# Schematics.net
KiCad netlist of a schematic drawn in EAGLE
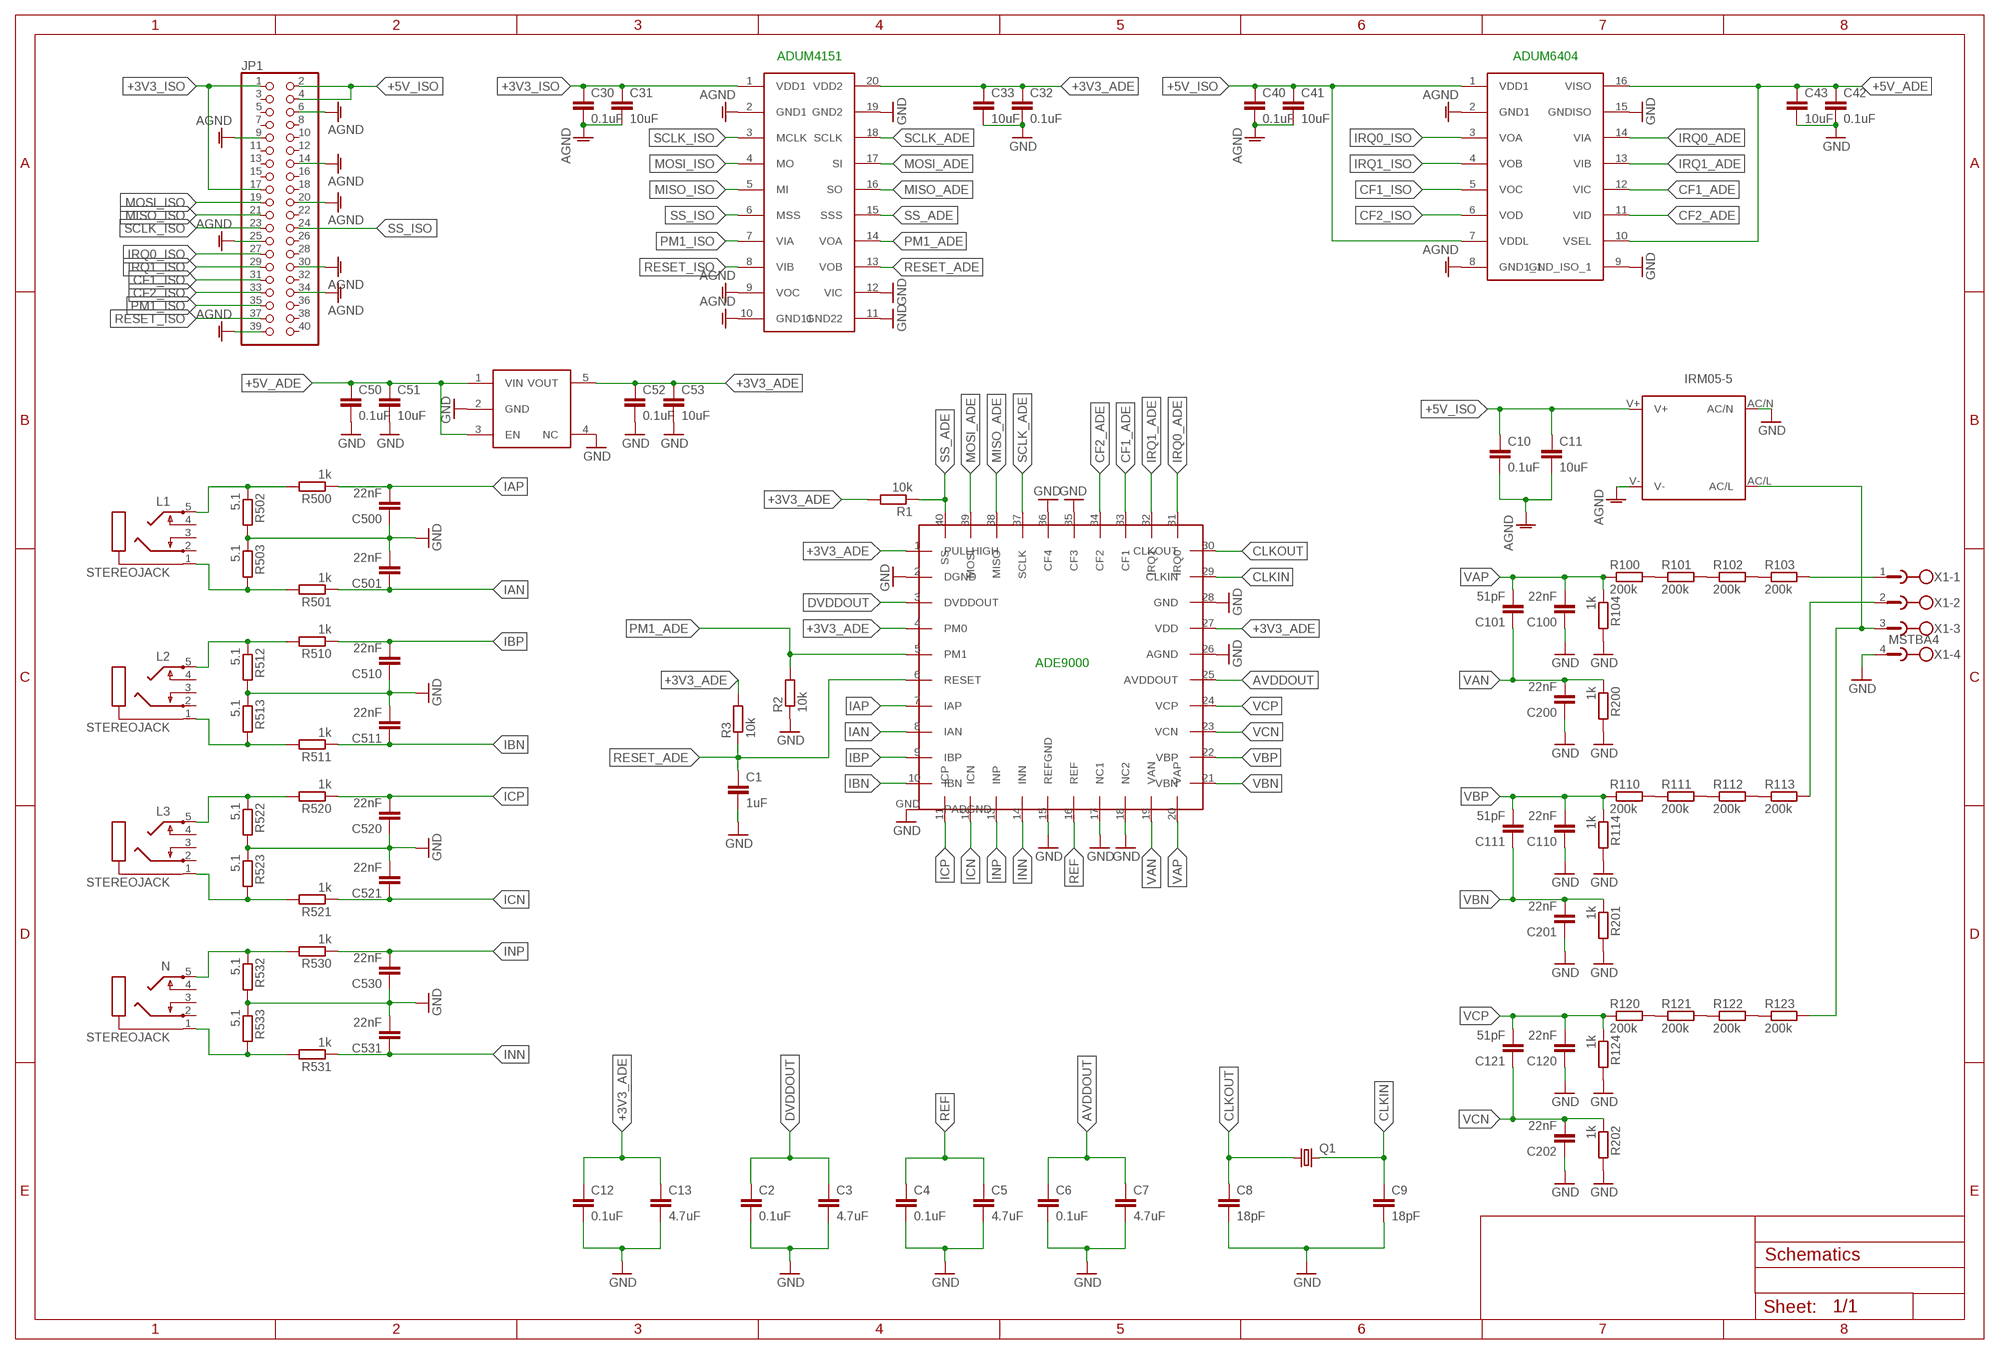
[diagram p0: schematic, sheet 1]

(export (version "E")
  (design (tool "Eeschema 10.0.6"))
  (components
    (comp (ref "ADE9000")
      (value "ADE9000")
      (footprint "eagle-import:LFCSP40")
      (libsource (lib "eagle-import") (part "ADE9000"))
    )
    (comp (ref "ADUM4151")
      (value "ADUM4151")
      (footprint "eagle-import:SOIC20R")
      (libsource (lib "eagle-import") (part "ADUM4151"))
    )
    (comp (ref "ADUM6404")
      (value "ADUM6404")
      (footprint "eagle-import:SOIC16R")
      (libsource (lib "eagle-import") (part "ADUM6404"))
    )
    (comp (ref "C1")
      (value "1uF")
      (footprint "eagle-import:C0805")
      (libsource (lib "eagle-import") (part "C-EUC0805"))
    )
    (comp (ref "C2")
      (value "0.1uF")
      (footprint "eagle-import:C0805")
      (libsource (lib "eagle-import") (part "C-EUC0805"))
    )
    (comp (ref "C3")
      (value "4.7uF")
      (footprint "eagle-import:C0805")
      (libsource (lib "eagle-import") (part "C-EUC0805"))
    )
    (comp (ref "C4")
      (value "0.1uF")
      (footprint "eagle-import:C0805")
      (libsource (lib "eagle-import") (part "C-EUC0805"))
    )
    (comp (ref "C5")
      (value "4.7uF")
      (footprint "eagle-import:C0805")
      (libsource (lib "eagle-import") (part "C-EUC0805"))
    )
    (comp (ref "C6")
      (value "0.1uF")
      (footprint "eagle-import:C0805")
      (libsource (lib "eagle-import") (part "C-EUC0805"))
    )
    (comp (ref "C7")
      (value "4.7uF")
      (footprint "eagle-import:C0805")
      (libsource (lib "eagle-import") (part "C-EUC0805"))
    )
    (comp (ref "C8")
      (value "18pF")
      (footprint "eagle-import:C0805")
      (libsource (lib "eagle-import") (part "C-EUC0805"))
    )
    (comp (ref "C9")
      (value "18pF")
      (footprint "eagle-import:C0805")
      (libsource (lib "eagle-import") (part "C-EUC0805"))
    )
    (comp (ref "C10")
      (value "0.1uF")
      (footprint "eagle-import:C0805")
      (libsource (lib "eagle-import") (part "C-EUC0805"))
    )
    (comp (ref "C11")
      (value "10uF")
      (footprint "eagle-import:C0805")
      (libsource (lib "eagle-import") (part "C-EUC0805"))
    )
    (comp (ref "C12")
      (value "0.1uF")
      (footprint "eagle-import:C0805")
      (libsource (lib "eagle-import") (part "C-EUC0805"))
    )
    (comp (ref "C13")
      (value "4.7uF")
      (footprint "eagle-import:C0805")
      (libsource (lib "eagle-import") (part "C-EUC0805"))
    )
    (comp (ref "C30")
      (value "0.1uF")
      (footprint "eagle-import:C0805")
      (libsource (lib "eagle-import") (part "C-EUC0805"))
    )
    (comp (ref "C31")
      (value "10uF")
      (footprint "eagle-import:C0805")
      (libsource (lib "eagle-import") (part "C-EUC0805"))
    )
    (comp (ref "C32")
      (value "0.1uF")
      (footprint "eagle-import:C0805")
      (libsource (lib "eagle-import") (part "C-EUC0805"))
    )
    (comp (ref "C33")
      (value "10uF")
      (footprint "eagle-import:C0805")
      (libsource (lib "eagle-import") (part "C-EUC0805"))
    )
    (comp (ref "C40")
      (value "0.1uF")
      (footprint "eagle-import:C0805")
      (libsource (lib "eagle-import") (part "C-EUC0805"))
    )
    (comp (ref "C41")
      (value "10uF")
      (footprint "eagle-import:C0805")
      (libsource (lib "eagle-import") (part "C-EUC0805"))
    )
    (comp (ref "C42")
      (value "0.1uF")
      (footprint "eagle-import:C0805")
      (libsource (lib "eagle-import") (part "C-EUC0805"))
    )
    (comp (ref "C43")
      (value "10uF")
      (footprint "eagle-import:C0805")
      (libsource (lib "eagle-import") (part "C-EUC0805"))
    )
    (comp (ref "C50")
      (value "0.1uF")
      (footprint "eagle-import:C0805")
      (libsource (lib "eagle-import") (part "C-EUC0805"))
    )
    (comp (ref "C51")
      (value "10uF")
      (footprint "eagle-import:C0805")
      (libsource (lib "eagle-import") (part "C-EUC0805"))
    )
    (comp (ref "C52")
      (value "0.1uF")
      (footprint "eagle-import:C0805")
      (libsource (lib "eagle-import") (part "C-EUC0805"))
    )
    (comp (ref "C53")
      (value "10uF")
      (footprint "eagle-import:C0805")
      (libsource (lib "eagle-import") (part "C-EUC0805"))
    )
    (comp (ref "C100")
      (value "22nF")
      (footprint "eagle-import:C0805")
      (libsource (lib "eagle-import") (part "C-EUC0805"))
    )
    (comp (ref "C101")
      (value "51pF")
      (footprint "eagle-import:C0805")
      (libsource (lib "eagle-import") (part "C-EUC0805"))
    )
    (comp (ref "C110")
      (value "22nF")
      (footprint "eagle-import:C0805")
      (libsource (lib "eagle-import") (part "C-EUC0805"))
    )
    (comp (ref "C111")
      (value "51pF")
      (footprint "eagle-import:C0805")
      (libsource (lib "eagle-import") (part "C-EUC0805"))
    )
    (comp (ref "C120")
      (value "22nF")
      (footprint "eagle-import:C0805")
      (libsource (lib "eagle-import") (part "C-EUC0805"))
    )
    (comp (ref "C121")
      (value "51pF")
      (footprint "eagle-import:C0805")
      (libsource (lib "eagle-import") (part "C-EUC0805"))
    )
    (comp (ref "C200")
      (value "22nF")
      (footprint "eagle-import:C0805")
      (libsource (lib "eagle-import") (part "C-EUC0805"))
    )
    (comp (ref "C201")
      (value "22nF")
      (footprint "eagle-import:C0805")
      (libsource (lib "eagle-import") (part "C-EUC0805"))
    )
    (comp (ref "C202")
      (value "22nF")
      (footprint "eagle-import:C0805")
      (libsource (lib "eagle-import") (part "C-EUC0805"))
    )
    (comp (ref "C500")
      (value "22nF")
      (footprint "eagle-import:C0805")
      (libsource (lib "eagle-import") (part "C-EUC0805"))
    )
    (comp (ref "C501")
      (value "22nF")
      (footprint "eagle-import:C0805")
      (libsource (lib "eagle-import") (part "C-EUC0805"))
    )
    (comp (ref "C510")
      (value "22nF")
      (footprint "eagle-import:C0805")
      (libsource (lib "eagle-import") (part "C-EUC0805"))
    )
    (comp (ref "C511")
      (value "22nF")
      (footprint "eagle-import:C0805")
      (libsource (lib "eagle-import") (part "C-EUC0805"))
    )
    (comp (ref "C520")
      (value "22nF")
      (footprint "eagle-import:C0805")
      (libsource (lib "eagle-import") (part "C-EUC0805"))
    )
    (comp (ref "C521")
      (value "22nF")
      (footprint "eagle-import:C0805")
      (libsource (lib "eagle-import") (part "C-EUC0805"))
    )
    (comp (ref "C530")
      (value "22nF")
      (footprint "eagle-import:C0805")
      (libsource (lib "eagle-import") (part "C-EUC0805"))
    )
    (comp (ref "C531")
      (value "22nF")
      (footprint "eagle-import:C0805")
      (libsource (lib "eagle-import") (part "C-EUC0805"))
    )
    (comp (ref "IRM05-5")
      (value "IRM_05/10")
      (footprint "eagle-import:IRM_05_10")
      (libsource (lib "eagle-import") (part "IRM_05/10"))
    )
    (comp (ref "JP1")
      (value "PINHD-2X20")
      (footprint "eagle-import:2X20")
      (libsource (lib "eagle-import") (part "PINHD-2X20"))
    )
    (comp (ref "L1")
      (value "STEREOJACK")
      (footprint "eagle-import:STX3100")
      (libsource (lib "eagle-import") (part "STEREOJACK"))
    )
    (comp (ref "L2")
      (value "STEREOJACK")
      (footprint "eagle-import:STX3100")
      (libsource (lib "eagle-import") (part "STEREOJACK"))
    )
    (comp (ref "L3")
      (value "STEREOJACK")
      (footprint "eagle-import:STX3100")
      (libsource (lib "eagle-import") (part "STEREOJACK"))
    )
    (comp (ref "N")
      (value "STEREOJACK")
      (footprint "eagle-import:STX3100")
      (libsource (lib "eagle-import") (part "STEREOJACK"))
    )
    (comp (ref "Q1")
      (value "CRYSTALCTS406")
      (footprint "eagle-import:CTS406")
      (libsource (lib "eagle-import") (part "CRYSTALCTS406"))
    )
    (comp (ref "R1")
      (value "10k")
      (footprint "eagle-import:M0805")
      (libsource (lib "eagle-import") (part "R-EU_M0805"))
    )
    (comp (ref "R2")
      (value "10k")
      (footprint "eagle-import:M0805")
      (libsource (lib "eagle-import") (part "R-EU_M0805"))
    )
    (comp (ref "R3")
      (value "10k")
      (footprint "eagle-import:M0805")
      (libsource (lib "eagle-import") (part "R-EU_M0805"))
    )
    (comp (ref "R100")
      (value "200k")
      (footprint "eagle-import:M1206")
      (libsource (lib "eagle-import") (part "R-EU_M1206"))
    )
    (comp (ref "R101")
      (value "200k")
      (footprint "eagle-import:M1206")
      (libsource (lib "eagle-import") (part "R-EU_M1206"))
    )
    (comp (ref "R102")
      (value "200k")
      (footprint "eagle-import:M1206")
      (libsource (lib "eagle-import") (part "R-EU_M1206"))
    )
    (comp (ref "R103")
      (value "200k")
      (footprint "eagle-import:M1206")
      (libsource (lib "eagle-import") (part "R-EU_M1206"))
    )
    (comp (ref "R104")
      (value "1k")
      (footprint "eagle-import:M0805")
      (libsource (lib "eagle-import") (part "R-EU_M0805"))
    )
    (comp (ref "R110")
      (value "200k")
      (footprint "eagle-import:M1206")
      (libsource (lib "eagle-import") (part "R-EU_M1206"))
    )
    (comp (ref "R111")
      (value "200k")
      (footprint "eagle-import:M1206")
      (libsource (lib "eagle-import") (part "R-EU_M1206"))
    )
    (comp (ref "R112")
      (value "200k")
      (footprint "eagle-import:M1206")
      (libsource (lib "eagle-import") (part "R-EU_M1206"))
    )
    (comp (ref "R113")
      (value "200k")
      (footprint "eagle-import:M1206")
      (libsource (lib "eagle-import") (part "R-EU_M1206"))
    )
    (comp (ref "R114")
      (value "1k")
      (footprint "eagle-import:M0805")
      (libsource (lib "eagle-import") (part "R-EU_M0805"))
    )
    (comp (ref "R120")
      (value "200k")
      (footprint "eagle-import:M1206")
      (libsource (lib "eagle-import") (part "R-EU_M1206"))
    )
    (comp (ref "R121")
      (value "200k")
      (footprint "eagle-import:M1206")
      (libsource (lib "eagle-import") (part "R-EU_M1206"))
    )
    (comp (ref "R122")
      (value "200k")
      (footprint "eagle-import:M1206")
      (libsource (lib "eagle-import") (part "R-EU_M1206"))
    )
    (comp (ref "R123")
      (value "200k")
      (footprint "eagle-import:M1206")
      (libsource (lib "eagle-import") (part "R-EU_M1206"))
    )
    (comp (ref "R124")
      (value "1k")
      (footprint "eagle-import:M0805")
      (libsource (lib "eagle-import") (part "R-EU_M0805"))
    )
    (comp (ref "R200")
      (value "1k")
      (footprint "eagle-import:M0805")
      (libsource (lib "eagle-import") (part "R-EU_M0805"))
    )
    (comp (ref "R201")
      (value "1k")
      (footprint "eagle-import:M0805")
      (libsource (lib "eagle-import") (part "R-EU_M0805"))
    )
    (comp (ref "R202")
      (value "1k")
      (footprint "eagle-import:M0805")
      (libsource (lib "eagle-import") (part "R-EU_M0805"))
    )
    (comp (ref "R500")
      (value "1k")
      (footprint "eagle-import:M0805")
      (libsource (lib "eagle-import") (part "R-EU_M0805"))
    )
    (comp (ref "R501")
      (value "1k")
      (footprint "eagle-import:M0805")
      (libsource (lib "eagle-import") (part "R-EU_M0805"))
    )
    (comp (ref "R502")
      (value "5.1")
      (footprint "eagle-import:M0805")
      (libsource (lib "eagle-import") (part "R-EU_M0805"))
    )
    (comp (ref "R503")
      (value "5.1")
      (footprint "eagle-import:M0805")
      (libsource (lib "eagle-import") (part "R-EU_M0805"))
    )
    (comp (ref "R510")
      (value "1k")
      (footprint "eagle-import:M0805")
      (libsource (lib "eagle-import") (part "R-EU_M0805"))
    )
    (comp (ref "R511")
      (value "1k")
      (footprint "eagle-import:M0805")
      (libsource (lib "eagle-import") (part "R-EU_M0805"))
    )
    (comp (ref "R512")
      (value "5.1")
      (footprint "eagle-import:M0805")
      (libsource (lib "eagle-import") (part "R-EU_M0805"))
    )
    (comp (ref "R513")
      (value "5.1")
      (footprint "eagle-import:M0805")
      (libsource (lib "eagle-import") (part "R-EU_M0805"))
    )
    (comp (ref "R520")
      (value "1k")
      (footprint "eagle-import:M0805")
      (libsource (lib "eagle-import") (part "R-EU_M0805"))
    )
    (comp (ref "R521")
      (value "1k")
      (footprint "eagle-import:M0805")
      (libsource (lib "eagle-import") (part "R-EU_M0805"))
    )
    (comp (ref "R522")
      (value "5.1")
      (footprint "eagle-import:M0805")
      (libsource (lib "eagle-import") (part "R-EU_M0805"))
    )
    (comp (ref "R523")
      (value "5.1")
      (footprint "eagle-import:M0805")
      (libsource (lib "eagle-import") (part "R-EU_M0805"))
    )
    (comp (ref "R530")
      (value "1k")
      (footprint "eagle-import:M0805")
      (libsource (lib "eagle-import") (part "R-EU_M0805"))
    )
    (comp (ref "R531")
      (value "1k")
      (footprint "eagle-import:M0805")
      (libsource (lib "eagle-import") (part "R-EU_M0805"))
    )
    (comp (ref "R532")
      (value "5.1")
      (footprint "eagle-import:M0805")
      (libsource (lib "eagle-import") (part "R-EU_M0805"))
    )
    (comp (ref "R533")
      (value "5.1")
      (footprint "eagle-import:M0805")
      (libsource (lib "eagle-import") (part "R-EU_M0805"))
    )
    (comp (ref "U$5")
      (value "ADP122AUJZ-3.3-R7")
      (footprint "eagle-import:TSOT23-5L")
      (libsource (lib "eagle-import") (part "ADP122AUJZ-3.3-R7"))
    )
    (comp (ref "X1")
      (value "MSTBA4")
      (footprint "eagle-import:MSTBA4")
      (fields (field (name "MF") "FARNELL") (field (name "MPN") "1757268"))
      (libsource (lib "eagle-import") (part "MSTBA4"))
    )
  )
  (nets
    (net (code "1") (name "+3V3_ADE") (class "Default")
      (node (ref "ADE9000") (pin "1") (pinfunction "PULLHIGH_1") (pintype "bidirectional"))
      (node (ref "ADE9000") (pin "27") (pinfunction "VDD_27") (pintype "bidirectional"))
      (node (ref "ADE9000") (pin "4") (pinfunction "PM0_4") (pintype "bidirectional"))
      (node (ref "ADUM4151") (pin "20") (pinfunction "VDD2_20") (pintype "bidirectional"))
      (node (ref "C12") (pin "1") (pinfunction "1_1") (pintype "passive"))
      (node (ref "C13") (pin "1") (pinfunction "1_1") (pintype "passive"))
      (node (ref "C32") (pin "1") (pinfunction "1_1") (pintype "passive"))
      (node (ref "C33") (pin "1") (pinfunction "1_1") (pintype "passive"))
      (node (ref "C52") (pin "1") (pinfunction "1_1") (pintype "passive"))
      (node (ref "C53") (pin "1") (pinfunction "1_1") (pintype "passive"))
      (node (ref "R1") (pin "2") (pinfunction "2_2") (pintype "passive"))
      (node (ref "R3") (pin "2") (pinfunction "2_2") (pintype "passive"))
      (node (ref "U$5") (pin "5") (pinfunction "VOUT_5") (pintype "bidirectional"))
    )
    (net (code "2") (name "+3V3_ISO") (class "Default")
      (node (ref "ADUM4151") (pin "1") (pinfunction "VDD1_1") (pintype "bidirectional"))
      (node (ref "C30") (pin "1") (pinfunction "1_1") (pintype "passive"))
      (node (ref "C31") (pin "1") (pinfunction "1_1") (pintype "passive"))
      (node (ref "JP1") (pin "1") (pinfunction "1_1") (pintype "passive"))
      (node (ref "JP1") (pin "17") (pinfunction "17_17") (pintype "passive"))
    )
    (net (code "3") (name "+5V_ADE") (class "Default")
      (node (ref "ADUM6404") (pin "10") (pinfunction "VSEL_10") (pintype "bidirectional"))
      (node (ref "ADUM6404") (pin "16") (pinfunction "VISO_16") (pintype "bidirectional"))
      (node (ref "C42") (pin "1") (pinfunction "1_1") (pintype "passive"))
      (node (ref "C43") (pin "1") (pinfunction "1_1") (pintype "passive"))
      (node (ref "C50") (pin "1") (pinfunction "1_1") (pintype "passive"))
      (node (ref "C51") (pin "1") (pinfunction "1_1") (pintype "passive"))
      (node (ref "U$5") (pin "1") (pinfunction "VIN_1") (pintype "bidirectional"))
      (node (ref "U$5") (pin "3") (pinfunction "EN_3") (pintype "bidirectional"))
    )
    (net (code "4") (name "+5V_ISO") (class "Default")
      (node (ref "ADUM6404") (pin "1") (pinfunction "VDD1_1") (pintype "bidirectional"))
      (node (ref "ADUM6404") (pin "7") (pinfunction "VDDL_7") (pintype "bidirectional"))
      (node (ref "C10") (pin "1") (pinfunction "1_1") (pintype "passive"))
      (node (ref "C11") (pin "1") (pinfunction "1_1") (pintype "passive"))
      (node (ref "C40") (pin "1") (pinfunction "1_1") (pintype "passive"))
      (node (ref "C41") (pin "1") (pinfunction "1_1") (pintype "passive"))
      (node (ref "IRM05-5") (pin "V+") (pinfunction "V+_V+") (pintype "output"))
      (node (ref "JP1") (pin "2") (pinfunction "2_2") (pintype "passive"))
      (node (ref "JP1") (pin "4") (pinfunction "4_4") (pintype "passive"))
    )
    (net (code "5") (name "AGND") (class "Default")
      (node (ref "ADUM4151") (pin "10") (pinfunction "GND11_10") (pintype "bidirectional"))
      (node (ref "ADUM4151") (pin "2") (pinfunction "GND1_2") (pintype "bidirectional"))
      (node (ref "ADUM4151") (pin "9") (pinfunction "VOC_9") (pintype "bidirectional"))
      (node (ref "ADUM6404") (pin "2") (pinfunction "GND1_2") (pintype "bidirectional"))
      (node (ref "ADUM6404") (pin "8") (pinfunction "GND1_1_8") (pintype "bidirectional"))
      (node (ref "C10") (pin "2") (pinfunction "2_2") (pintype "passive"))
      (node (ref "C11") (pin "2") (pinfunction "2_2") (pintype "passive"))
      (node (ref "C30") (pin "2") (pinfunction "2_2") (pintype "passive"))
      (node (ref "C31") (pin "2") (pinfunction "2_2") (pintype "passive"))
      (node (ref "C40") (pin "2") (pinfunction "2_2") (pintype "passive"))
      (node (ref "C41") (pin "2") (pinfunction "2_2") (pintype "passive"))
      (node (ref "IRM05-5") (pin "V-") (pinfunction "V-_V-") (pintype "output"))
      (node (ref "JP1") (pin "14") (pinfunction "14_14") (pintype "passive"))
      (node (ref "JP1") (pin "20") (pinfunction "20_20") (pintype "passive"))
      (node (ref "JP1") (pin "25") (pinfunction "25_25") (pintype "passive"))
      (node (ref "JP1") (pin "30") (pinfunction "30_30") (pintype "passive"))
      (node (ref "JP1") (pin "34") (pinfunction "34_34") (pintype "passive"))
      (node (ref "JP1") (pin "39") (pinfunction "39_39") (pintype "passive"))
      (node (ref "JP1") (pin "6") (pinfunction "6_6") (pintype "passive"))
      (node (ref "JP1") (pin "9") (pinfunction "9_9") (pintype "passive"))
    )
    (net (code "6") (name "AVDDOUT") (class "Default")
      (node (ref "ADE9000") (pin "25") (pinfunction "AVDDOUT_25") (pintype "bidirectional"))
      (node (ref "C6") (pin "1") (pinfunction "1_1") (pintype "passive"))
      (node (ref "C7") (pin "1") (pinfunction "1_1") (pintype "passive"))
    )
    (net (code "7") (name "CF1_ADE") (class "Default")
      (node (ref "ADE9000") (pin "33") (pinfunction "CF1_33") (pintype "bidirectional"))
      (node (ref "ADUM6404") (pin "12") (pinfunction "VIC_12") (pintype "bidirectional"))
    )
    (net (code "8") (name "CF1_ISO") (class "Default")
      (node (ref "ADUM6404") (pin "5") (pinfunction "VOC_5") (pintype "bidirectional"))
      (node (ref "JP1") (pin "31") (pinfunction "31_31") (pintype "passive"))
    )
    (net (code "9") (name "CF2_ADE") (class "Default")
      (node (ref "ADE9000") (pin "34") (pinfunction "CF2_34") (pintype "bidirectional"))
      (node (ref "ADUM6404") (pin "11") (pinfunction "VID_11") (pintype "bidirectional"))
    )
    (net (code "10") (name "CF2_ISO") (class "Default")
      (node (ref "ADUM6404") (pin "6") (pinfunction "VOD_6") (pintype "bidirectional"))
      (node (ref "JP1") (pin "33") (pinfunction "33_33") (pintype "passive"))
    )
    (net (code "11") (name "CLKIN") (class "Default")
      (node (ref "ADE9000") (pin "29") (pinfunction "CLKIN_29") (pintype "bidirectional"))
      (node (ref "C9") (pin "1") (pinfunction "1_1") (pintype "passive"))
      (node (ref "Q1") (pin "3") (pinfunction "2_3") (pintype "passive"))
    )
    (net (code "12") (name "CLKOUT") (class "Default")
      (node (ref "ADE9000") (pin "30") (pinfunction "CLKOUT_30") (pintype "bidirectional"))
      (node (ref "C8") (pin "1") (pinfunction "1_1") (pintype "passive"))
      (node (ref "Q1") (pin "1") (pinfunction "1_1") (pintype "passive"))
    )
    (net (code "13") (name "DVDDOUT") (class "Default")
      (node (ref "ADE9000") (pin "3") (pinfunction "DVDDOUT_3") (pintype "bidirectional"))
      (node (ref "C2") (pin "1") (pinfunction "1_1") (pintype "passive"))
      (node (ref "C3") (pin "1") (pinfunction "1_1") (pintype "passive"))
    )
    (net (code "14") (name "GND") (class "Default")
      (node (ref "ADE9000") (pin "15") (pinfunction "REFGND_15") (pintype "bidirectional"))
      (node (ref "ADE9000") (pin "17") (pinfunction "NC1_17") (pintype "bidirectional"))
      (node (ref "ADE9000") (pin "18") (pinfunction "NC2_18") (pintype "bidirectional"))
      (node (ref "ADE9000") (pin "2") (pinfunction "DGND_2") (pintype "bidirectional"))
      (node (ref "ADE9000") (pin "26") (pinfunction "AGND_26") (pintype "bidirectional"))
      (node (ref "ADE9000") (pin "28") (pinfunction "GND_28") (pintype "bidirectional"))
      (node (ref "ADE9000") (pin "35") (pinfunction "CF3_35") (pintype "bidirectional"))
      (node (ref "ADE9000") (pin "36") (pinfunction "CF4_36") (pintype "bidirectional"))
      (node (ref "ADE9000") (pin "GND") (pinfunction "PADGND_GND") (pintype "bidirectional"))
      (node (ref "ADUM4151") (pin "11") (pinfunction "GND22_11") (pintype "bidirectional"))
      (node (ref "ADUM4151") (pin "12") (pinfunction "VIC_12") (pintype "bidirectional"))
      (node (ref "ADUM4151") (pin "19") (pinfunction "GND2_19") (pintype "bidirectional"))
      (node (ref "ADUM6404") (pin "15") (pinfunction "GNDISO_15") (pintype "bidirectional"))
      (node (ref "ADUM6404") (pin "9") (pinfunction "GND_ISO_1_9") (pintype "bidirectional"))
      (node (ref "C1") (pin "2") (pinfunction "2_2") (pintype "passive"))
      (node (ref "C100") (pin "1") (pinfunction "1_1") (pintype "passive"))
      (node (ref "C110") (pin "1") (pinfunction "1_1") (pintype "passive"))
      (node (ref "C12") (pin "2") (pinfunction "2_2") (pintype "passive"))
      (node (ref "C120") (pin "1") (pinfunction "1_1") (pintype "passive"))
      (node (ref "C13") (pin "2") (pinfunction "2_2") (pintype "passive"))
      (node (ref "C2") (pin "2") (pinfunction "2_2") (pintype "passive"))
      (node (ref "C200") (pin "1") (pinfunction "1_1") (pintype "passive"))
      (node (ref "C201") (pin "1") (pinfunction "1_1") (pintype "passive"))
      (node (ref "C202") (pin "1") (pinfunction "1_1") (pintype "passive"))
      (node (ref "C3") (pin "2") (pinfunction "2_2") (pintype "passive"))
      (node (ref "C32") (pin "2") (pinfunction "2_2") (pintype "passive"))
      (node (ref "C33") (pin "2") (pinfunction "2_2") (pintype "passive"))
      (node (ref "C4") (pin "2") (pinfunction "2_2") (pintype "passive"))
      (node (ref "C42") (pin "2") (pinfunction "2_2") (pintype "passive"))
      (node (ref "C43") (pin "2") (pinfunction "2_2") (pintype "passive"))
      (node (ref "C5") (pin "2") (pinfunction "2_2") (pintype "passive"))
      (node (ref "C50") (pin "2") (pinfunction "2_2") (pintype "passive"))
      (node (ref "C500") (pin "1") (pinfunction "1_1") (pintype "passive"))
      (node (ref "C501") (pin "2") (pinfunction "2_2") (pintype "passive"))
      (node (ref "C51") (pin "2") (pinfunction "2_2") (pintype "passive"))
      (node (ref "C510") (pin "1") (pinfunction "1_1") (pintype "passive"))
      (node (ref "C511") (pin "2") (pinfunction "2_2") (pintype "passive"))
      (node (ref "C52") (pin "2") (pinfunction "2_2") (pintype "passive"))
      (node (ref "C520") (pin "1") (pinfunction "1_1") (pintype "passive"))
      (node (ref "C521") (pin "2") (pinfunction "2_2") (pintype "passive"))
      (node (ref "C53") (pin "2") (pinfunction "2_2") (pintype "passive"))
      (node (ref "C530") (pin "1") (pinfunction "1_1") (pintype "passive"))
      (node (ref "C531") (pin "2") (pinfunction "2_2") (pintype "passive"))
      (node (ref "C6") (pin "2") (pinfunction "2_2") (pintype "passive"))
      (node (ref "C7") (pin "2") (pinfunction "2_2") (pintype "passive"))
      (node (ref "C8") (pin "2") (pinfunction "2_2") (pintype "passive"))
      (node (ref "C9") (pin "2") (pinfunction "2_2") (pintype "passive"))
      (node (ref "IRM05-5") (pin "AC/N") (pinfunction "AC/N_AC/N") (pintype "input"))
      (node (ref "R104") (pin "2") (pinfunction "2_2") (pintype "passive"))
      (node (ref "R114") (pin "2") (pinfunction "2_2") (pintype "passive"))
      (node (ref "R124") (pin "2") (pinfunction "2_2") (pintype "passive"))
      (node (ref "R2") (pin "1") (pinfunction "1_1") (pintype "passive"))
      (node (ref "R200") (pin "2") (pinfunction "2_2") (pintype "passive"))
      (node (ref "R201") (pin "2") (pinfunction "2_2") (pintype "passive"))
      (node (ref "R202") (pin "2") (pinfunction "2_2") (pintype "passive"))
      (node (ref "R502") (pin "2") (pinfunction "2_2") (pintype "passive"))
      (node (ref "R503") (pin "1") (pinfunction "1_1") (pintype "passive"))
      (node (ref "R512") (pin "2") (pinfunction "2_2") (pintype "passive"))
      (node (ref "R513") (pin "1") (pinfunction "1_1") (pintype "passive"))
      (node (ref "R522") (pin "2") (pinfunction "2_2") (pintype "passive"))
      (node (ref "R523") (pin "1") (pinfunction "1_1") (pintype "passive"))
      (node (ref "R532") (pin "2") (pinfunction "2_2") (pintype "passive"))
      (node (ref "R533") (pin "1") (pinfunction "1_1") (pintype "passive"))
      (node (ref "U$5") (pin "2") (pinfunction "GND_2") (pintype "bidirectional"))
      (node (ref "U$5") (pin "4") (pinfunction "NC_4") (pintype "bidirectional"))
      (node (ref "X1") (pin "4") (pinfunction "1_4") (pintype "passive"))
    )
    (net (code "15") (name "IAN") (class "Default")
      (node (ref "ADE9000") (pin "8") (pinfunction "IAN_8") (pintype "bidirectional"))
      (node (ref "C501") (pin "1") (pinfunction "1_1") (pintype "passive"))
      (node (ref "R501") (pin "1") (pinfunction "1_1") (pintype "passive"))
    )
    (net (code "16") (name "IAP") (class "Default")
      (node (ref "ADE9000") (pin "7") (pinfunction "IAP_7") (pintype "bidirectional"))
      (node (ref "C500") (pin "2") (pinfunction "2_2") (pintype "passive"))
      (node (ref "R500") (pin "1") (pinfunction "1_1") (pintype "passive"))
    )
    (net (code "17") (name "IBN") (class "Default")
      (node (ref "ADE9000") (pin "10") (pinfunction "IBN_10") (pintype "bidirectional"))
      (node (ref "C511") (pin "1") (pinfunction "1_1") (pintype "passive"))
      (node (ref "R511") (pin "1") (pinfunction "1_1") (pintype "passive"))
    )
    (net (code "18") (name "IBP") (class "Default")
      (node (ref "ADE9000") (pin "9") (pinfunction "IBP_9") (pintype "bidirectional"))
      (node (ref "C510") (pin "2") (pinfunction "2_2") (pintype "passive"))
      (node (ref "R510") (pin "1") (pinfunction "1_1") (pintype "passive"))
    )
    (net (code "19") (name "ICN") (class "Default")
      (node (ref "ADE9000") (pin "12") (pinfunction "ICN_12") (pintype "bidirectional"))
      (node (ref "C521") (pin "1") (pinfunction "1_1") (pintype "passive"))
      (node (ref "R521") (pin "1") (pinfunction "1_1") (pintype "passive"))
    )
    (net (code "20") (name "ICP") (class "Default")
      (node (ref "ADE9000") (pin "11") (pinfunction "ICP_11") (pintype "bidirectional"))
      (node (ref "C520") (pin "2") (pinfunction "2_2") (pintype "passive"))
      (node (ref "R520") (pin "1") (pinfunction "1_1") (pintype "passive"))
    )
    (net (code "21") (name "INN") (class "Default")
      (node (ref "ADE9000") (pin "14") (pinfunction "INN_14") (pintype "bidirectional"))
      (node (ref "C531") (pin "1") (pinfunction "1_1") (pintype "passive"))
      (node (ref "R531") (pin "1") (pinfunction "1_1") (pintype "passive"))
    )
    (net (code "22") (name "INP") (class "Default")
      (node (ref "ADE9000") (pin "13") (pinfunction "INP_13") (pintype "bidirectional"))
      (node (ref "C530") (pin "2") (pinfunction "2_2") (pintype "passive"))
      (node (ref "R530") (pin "1") (pinfunction "1_1") (pintype "passive"))
    )
    (net (code "23") (name "IRQ0_ADE") (class "Default")
      (node (ref "ADE9000") (pin "31") (pinfunction "IRQ0_31") (pintype "bidirectional"))
      (node (ref "ADUM6404") (pin "14") (pinfunction "VIA_14") (pintype "bidirectional"))
    )
    (net (code "24") (name "IRQ0_ISO") (class "Default")
      (node (ref "ADUM6404") (pin "3") (pinfunction "VOA_3") (pintype "bidirectional"))
      (node (ref "JP1") (pin "27") (pinfunction "27_27") (pintype "passive"))
    )
    (net (code "25") (name "IRQ1_ADE") (class "Default")
      (node (ref "ADE9000") (pin "32") (pinfunction "IRQ1_32") (pintype "bidirectional"))
      (node (ref "ADUM6404") (pin "13") (pinfunction "VIB_13") (pintype "bidirectional"))
    )
    (net (code "26") (name "IRQ1_ISO") (class "Default")
      (node (ref "ADUM6404") (pin "4") (pinfunction "VOB_4") (pintype "bidirectional"))
      (node (ref "JP1") (pin "29") (pinfunction "29_29") (pintype "passive"))
    )
    (net (code "27") (name "MISO_ADE") (class "Default")
      (node (ref "ADE9000") (pin "38") (pinfunction "MISO_38") (pintype "bidirectional"))
      (node (ref "ADUM4151") (pin "16") (pinfunction "SO_16") (pintype "bidirectional"))
    )
    (net (code "28") (name "MISO_ISO") (class "Default")
      (node (ref "ADUM4151") (pin "5") (pinfunction "MI_5") (pintype "bidirectional"))
      (node (ref "JP1") (pin "21") (pinfunction "21_21") (pintype "passive"))
    )
    (net (code "29") (name "MOSI_ADE") (class "Default")
      (node (ref "ADE9000") (pin "39") (pinfunction "MOSI_39") (pintype "bidirectional"))
      (node (ref "ADUM4151") (pin "17") (pinfunction "SI_17") (pintype "bidirectional"))
    )
    (net (code "30") (name "MOSI_ISO") (class "Default")
      (node (ref "ADUM4151") (pin "4") (pinfunction "MO_4") (pintype "bidirectional"))
      (node (ref "JP1") (pin "19") (pinfunction "19_19") (pintype "passive"))
    )
    (net (code "31") (name "Net-(L1-Pad1)") (class "Default")
      (node (ref "L1") (pin "1") (pinfunction "1_1") (pintype "passive"))
      (node (ref "R501") (pin "2") (pinfunction "2_2") (pintype "passive"))
      (node (ref "R503") (pin "2") (pinfunction "2_2") (pintype "passive"))
    )
    (net (code "32") (name "Net-(L1-Pad5)") (class "Default")
      (node (ref "L1") (pin "5") (pinfunction "5_5") (pintype "passive"))
      (node (ref "R500") (pin "2") (pinfunction "2_2") (pintype "passive"))
      (node (ref "R502") (pin "1") (pinfunction "1_1") (pintype "passive"))
    )
    (net (code "33") (name "Net-(L2-Pad1)") (class "Default")
      (node (ref "L2") (pin "1") (pinfunction "1_1") (pintype "passive"))
      (node (ref "R511") (pin "2") (pinfunction "2_2") (pintype "passive"))
      (node (ref "R513") (pin "2") (pinfunction "2_2") (pintype "passive"))
    )
    (net (code "34") (name "Net-(L2-Pad5)") (class "Default")
      (node (ref "L2") (pin "5") (pinfunction "5_5") (pintype "passive"))
      (node (ref "R510") (pin "2") (pinfunction "2_2") (pintype "passive"))
      (node (ref "R512") (pin "1") (pinfunction "1_1") (pintype "passive"))
    )
    (net (code "35") (name "Net-(L3-Pad1)") (class "Default")
      (node (ref "L3") (pin "1") (pinfunction "1_1") (pintype "passive"))
      (node (ref "R521") (pin "2") (pinfunction "2_2") (pintype "passive"))
      (node (ref "R523") (pin "2") (pinfunction "2_2") (pintype "passive"))
    )
    (net (code "36") (name "Net-(L3-Pad5)") (class "Default")
      (node (ref "L3") (pin "5") (pinfunction "5_5") (pintype "passive"))
      (node (ref "R520") (pin "2") (pinfunction "2_2") (pintype "passive"))
      (node (ref "R522") (pin "1") (pinfunction "1_1") (pintype "passive"))
    )
    (net (code "37") (name "Net-(N-Pad1)") (class "Default")
      (node (ref "N") (pin "1") (pinfunction "1_1") (pintype "passive"))
      (node (ref "R531") (pin "2") (pinfunction "2_2") (pintype "passive"))
      (node (ref "R533") (pin "2") (pinfunction "2_2") (pintype "passive"))
    )
    (net (code "38") (name "Net-(N-Pad5)") (class "Default")
      (node (ref "N") (pin "5") (pinfunction "5_5") (pintype "passive"))
      (node (ref "R530") (pin "2") (pinfunction "2_2") (pintype "passive"))
      (node (ref "R532") (pin "1") (pinfunction "1_1") (pintype "passive"))
    )
    (net (code "39") (name "Net-(R100-Pad2)") (class "Default")
      (node (ref "R100") (pin "2") (pinfunction "2_2") (pintype "passive"))
      (node (ref "R101") (pin "1") (pinfunction "1_1") (pintype "passive"))
    )
    (net (code "40") (name "Net-(R101-Pad2)") (class "Default")
      (node (ref "R101") (pin "2") (pinfunction "2_2") (pintype "passive"))
      (node (ref "R102") (pin "1") (pinfunction "1_1") (pintype "passive"))
    )
    (net (code "41") (name "Net-(R102-Pad2)") (class "Default")
      (node (ref "R102") (pin "2") (pinfunction "2_2") (pintype "passive"))
      (node (ref "R103") (pin "1") (pinfunction "1_1") (pintype "passive"))
    )
    (net (code "42") (name "Net-(R103-Pad2)") (class "Default")
      (node (ref "R103") (pin "2") (pinfunction "2_2") (pintype "passive"))
      (node (ref "X1") (pin "1") (pinfunction "1_1") (pintype "passive"))
    )
    (net (code "43") (name "Net-(R110-Pad2)") (class "Default")
      (node (ref "R110") (pin "2") (pinfunction "2_2") (pintype "passive"))
      (node (ref "R111") (pin "1") (pinfunction "1_1") (pintype "passive"))
    )
    (net (code "44") (name "Net-(R111-Pad2)") (class "Default")
      (node (ref "R111") (pin "2") (pinfunction "2_2") (pintype "passive"))
      (node (ref "R112") (pin "1") (pinfunction "1_1") (pintype "passive"))
    )
    (net (code "45") (name "Net-(R112-Pad2)") (class "Default")
      (node (ref "R112") (pin "2") (pinfunction "2_2") (pintype "passive"))
      (node (ref "R113") (pin "1") (pinfunction "1_1") (pintype "passive"))
    )
    (net (code "46") (name "Net-(R120-Pad2)") (class "Default")
      (node (ref "R120") (pin "2") (pinfunction "2_2") (pintype "passive"))
      (node (ref "R121") (pin "1") (pinfunction "1_1") (pintype "passive"))
    )
    (net (code "47") (name "Net-(R121-Pad2)") (class "Default")
      (node (ref "R121") (pin "2") (pinfunction "2_2") (pintype "passive"))
      (node (ref "R122") (pin "1") (pinfunction "1_1") (pintype "passive"))
    )
    (net (code "48") (name "Net-(R122-Pad2)") (class "Default")
      (node (ref "R122") (pin "2") (pinfunction "2_2") (pintype "passive"))
      (node (ref "R123") (pin "1") (pinfunction "1_1") (pintype "passive"))
    )
    (net (code "49") (name "Net-(X1B-1)") (class "Default")
      (node (ref "R113") (pin "2") (pinfunction "2_2") (pintype "passive"))
      (node (ref "X1") (pin "2") (pinfunction "1_2") (pintype "passive"))
    )
    (net (code "50") (name "Net-(X1C-1)") (class "Default")
      (node (ref "IRM05-5") (pin "AC/L") (pinfunction "AC/L_AC/L") (pintype "input"))
      (node (ref "R123") (pin "2") (pinfunction "2_2") (pintype "passive"))
      (node (ref "X1") (pin "3") (pinfunction "1_3") (pintype "passive"))
    )
    (net (code "51") (name "PM1_ADE") (class "Default")
      (node (ref "ADE9000") (pin "5") (pinfunction "PM1_5") (pintype "bidirectional"))
      (node (ref "ADUM4151") (pin "14") (pinfunction "VOA_14") (pintype "bidirectional"))
      (node (ref "R2") (pin "2") (pinfunction "2_2") (pintype "passive"))
    )
    (net (code "52") (name "PM1_ISO") (class "Default")
      (node (ref "ADUM4151") (pin "7") (pinfunction "VIA_7") (pintype "bidirectional"))
      (node (ref "JP1") (pin "35") (pinfunction "35_35") (pintype "passive"))
    )
    (net (code "53") (name "REF") (class "Default")
      (node (ref "ADE9000") (pin "16") (pinfunction "REF_16") (pintype "bidirectional"))
      (node (ref "C4") (pin "1") (pinfunction "1_1") (pintype "passive"))
      (node (ref "C5") (pin "1") (pinfunction "1_1") (pintype "passive"))
    )
    (net (code "54") (name "RESET_ADE") (class "Default")
      (node (ref "ADE9000") (pin "6") (pinfunction "RESET_6") (pintype "bidirectional"))
      (node (ref "ADUM4151") (pin "13") (pinfunction "VOB_13") (pintype "bidirectional"))
      (node (ref "C1") (pin "1") (pinfunction "1_1") (pintype "passive"))
      (node (ref "R3") (pin "1") (pinfunction "1_1") (pintype "passive"))
    )
    (net (code "55") (name "RESET_ISO") (class "Default")
      (node (ref "ADUM4151") (pin "8") (pinfunction "VIB_8") (pintype "bidirectional"))
      (node (ref "JP1") (pin "37") (pinfunction "37_37") (pintype "passive"))
    )
    (net (code "56") (name "SCLK_ADE") (class "Default")
      (node (ref "ADE9000") (pin "37") (pinfunction "SCLK_37") (pintype "bidirectional"))
      (node (ref "ADUM4151") (pin "18") (pinfunction "SCLK_18") (pintype "bidirectional"))
    )
    (net (code "57") (name "SCLK_ISO") (class "Default")
      (node (ref "ADUM4151") (pin "3") (pinfunction "MCLK_3") (pintype "bidirectional"))
      (node (ref "JP1") (pin "23") (pinfunction "23_23") (pintype "passive"))
    )
    (net (code "58") (name "SS_ADE") (class "Default")
      (node (ref "ADE9000") (pin "40") (pinfunction "SS_40") (pintype "bidirectional"))
      (node (ref "ADUM4151") (pin "15") (pinfunction "SSS_15") (pintype "bidirectional"))
      (node (ref "R1") (pin "1") (pinfunction "1_1") (pintype "passive"))
    )
    (net (code "59") (name "SS_ISO") (class "Default")
      (node (ref "ADUM4151") (pin "6") (pinfunction "MSS_6") (pintype "bidirectional"))
      (node (ref "JP1") (pin "24") (pinfunction "24_24") (pintype "passive"))
    )
    (net (code "60") (name "VAN") (class "Default")
      (node (ref "ADE9000") (pin "19") (pinfunction "VAN_19") (pintype "bidirectional"))
      (node (ref "C101") (pin "1") (pinfunction "1_1") (pintype "passive"))
      (node (ref "C200") (pin "2") (pinfunction "2_2") (pintype "passive"))
      (node (ref "R200") (pin "1") (pinfunction "1_1") (pintype "passive"))
    )
    (net (code "61") (name "VAP") (class "Default")
      (node (ref "ADE9000") (pin "20") (pinfunction "VAP_20") (pintype "bidirectional"))
      (node (ref "C100") (pin "2") (pinfunction "2_2") (pintype "passive"))
      (node (ref "C101") (pin "2") (pinfunction "2_2") (pintype "passive"))
      (node (ref "R100") (pin "1") (pinfunction "1_1") (pintype "passive"))
      (node (ref "R104") (pin "1") (pinfunction "1_1") (pintype "passive"))
    )
    (net (code "62") (name "VBN") (class "Default")
      (node (ref "ADE9000") (pin "21") (pinfunction "VBN_21") (pintype "bidirectional"))
      (node (ref "C111") (pin "1") (pinfunction "1_1") (pintype "passive"))
      (node (ref "C201") (pin "2") (pinfunction "2_2") (pintype "passive"))
      (node (ref "R201") (pin "1") (pinfunction "1_1") (pintype "passive"))
    )
    (net (code "63") (name "VBP") (class "Default")
      (node (ref "ADE9000") (pin "22") (pinfunction "VBP_22") (pintype "bidirectional"))
      (node (ref "C110") (pin "2") (pinfunction "2_2") (pintype "passive"))
      (node (ref "C111") (pin "2") (pinfunction "2_2") (pintype "passive"))
      (node (ref "R110") (pin "1") (pinfunction "1_1") (pintype "passive"))
      (node (ref "R114") (pin "1") (pinfunction "1_1") (pintype "passive"))
    )
    (net (code "64") (name "VCN") (class "Default")
      (node (ref "ADE9000") (pin "23") (pinfunction "VCN_23") (pintype "bidirectional"))
      (node (ref "C121") (pin "1") (pinfunction "1_1") (pintype "passive"))
      (node (ref "C202") (pin "2") (pinfunction "2_2") (pintype "passive"))
      (node (ref "R202") (pin "1") (pinfunction "1_1") (pintype "passive"))
    )
    (net (code "65") (name "VCP") (class "Default")
      (node (ref "ADE9000") (pin "24") (pinfunction "VCP_24") (pintype "bidirectional"))
      (node (ref "C120") (pin "2") (pinfunction "2_2") (pintype "passive"))
      (node (ref "C121") (pin "2") (pinfunction "2_2") (pintype "passive"))
      (node (ref "R120") (pin "1") (pinfunction "1_1") (pintype "passive"))
      (node (ref "R124") (pin "1") (pinfunction "1_1") (pintype "passive"))
    )
    (net (code "66") (name "unconnected-(JP1-Pad3)") (class "Default")
      (node (ref "JP1") (pin "3") (pinfunction "3_3") (pintype "passive"))
    )
    (net (code "67") (name "unconnected-(JP1-Pad5)") (class "Default")
      (node (ref "JP1") (pin "5") (pinfunction "5_5") (pintype "passive"))
    )
    (net (code "68") (name "unconnected-(JP1-Pad7)") (class "Default")
      (node (ref "JP1") (pin "7") (pinfunction "7_7") (pintype "passive"))
    )
    (net (code "69") (name "unconnected-(JP1-Pad8)") (class "Default")
      (node (ref "JP1") (pin "8") (pinfunction "8_8") (pintype "passive"))
    )
    (net (code "70") (name "unconnected-(JP1-Pad10)") (class "Default")
      (node (ref "JP1") (pin "10") (pinfunction "10_10") (pintype "passive"))
    )
    (net (code "71") (name "unconnected-(JP1-Pad11)") (class "Default")
      (node (ref "JP1") (pin "11") (pinfunction "11_11") (pintype "passive"))
    )
    (net (code "72") (name "unconnected-(JP1-Pad12)") (class "Default")
      (node (ref "JP1") (pin "12") (pinfunction "12_12") (pintype "passive"))
    )
    (net (code "73") (name "unconnected-(JP1-Pad13)") (class "Default")
      (node (ref "JP1") (pin "13") (pinfunction "13_13") (pintype "passive"))
    )
    (net (code "74") (name "unconnected-(JP1-Pad15)") (class "Default")
      (node (ref "JP1") (pin "15") (pinfunction "15_15") (pintype "passive"))
    )
    (net (code "75") (name "unconnected-(JP1-Pad16)") (class "Default")
      (node (ref "JP1") (pin "16") (pinfunction "16_16") (pintype "passive"))
    )
    (net (code "76") (name "unconnected-(JP1-Pad18)") (class "Default")
      (node (ref "JP1") (pin "18") (pinfunction "18_18") (pintype "passive"))
    )
    (net (code "77") (name "unconnected-(JP1-Pad22)") (class "Default")
      (node (ref "JP1") (pin "22") (pinfunction "22_22") (pintype "passive"))
    )
    (net (code "78") (name "unconnected-(JP1-Pad26)") (class "Default")
      (node (ref "JP1") (pin "26") (pinfunction "26_26") (pintype "passive"))
    )
    (net (code "79") (name "unconnected-(JP1-Pad28)") (class "Default")
      (node (ref "JP1") (pin "28") (pinfunction "28_28") (pintype "passive"))
    )
    (net (code "80") (name "unconnected-(JP1-Pad32)") (class "Default")
      (node (ref "JP1") (pin "32") (pinfunction "32_32") (pintype "passive"))
    )
    (net (code "81") (name "unconnected-(JP1-Pad36)") (class "Default")
      (node (ref "JP1") (pin "36") (pinfunction "36_36") (pintype "passive"))
    )
    (net (code "82") (name "unconnected-(JP1-Pad38)") (class "Default")
      (node (ref "JP1") (pin "38") (pinfunction "38_38") (pintype "passive"))
    )
    (net (code "83") (name "unconnected-(JP1-Pad40)") (class "Default")
      (node (ref "JP1") (pin "40") (pinfunction "40_40") (pintype "passive"))
    )
    (net (code "84") (name "unconnected-(L1-Pad2)") (class "Default")
      (node (ref "L1") (pin "2") (pinfunction "2_2") (pintype "passive"))
    )
    (net (code "85") (name "unconnected-(L1-Pad3)") (class "Default")
      (node (ref "L1") (pin "3") (pinfunction "3_3") (pintype "passive"))
    )
    (net (code "86") (name "unconnected-(L1-Pad4)") (class "Default")
      (node (ref "L1") (pin "4") (pinfunction "4_4") (pintype "passive"))
    )
    (net (code "87") (name "unconnected-(L2-Pad2)") (class "Default")
      (node (ref "L2") (pin "2") (pinfunction "2_2") (pintype "passive"))
    )
    (net (code "88") (name "unconnected-(L2-Pad3)") (class "Default")
      (node (ref "L2") (pin "3") (pinfunction "3_3") (pintype "passive"))
    )
    (net (code "89") (name "unconnected-(L2-Pad4)") (class "Default")
      (node (ref "L2") (pin "4") (pinfunction "4_4") (pintype "passive"))
    )
    (net (code "90") (name "unconnected-(L3-Pad2)") (class "Default")
      (node (ref "L3") (pin "2") (pinfunction "2_2") (pintype "passive"))
    )
    (net (code "91") (name "unconnected-(L3-Pad3)") (class "Default")
      (node (ref "L3") (pin "3") (pinfunction "3_3") (pintype "passive"))
    )
    (net (code "92") (name "unconnected-(L3-Pad4)") (class "Default")
      (node (ref "L3") (pin "4") (pinfunction "4_4") (pintype "passive"))
    )
    (net (code "93") (name "unconnected-(N-Pad2)") (class "Default")
      (node (ref "N") (pin "2") (pinfunction "2_2") (pintype "passive"))
    )
    (net (code "94") (name "unconnected-(N-Pad3)") (class "Default")
      (node (ref "N") (pin "3") (pinfunction "3_3") (pintype "passive"))
    )
    (net (code "95") (name "unconnected-(N-Pad4)") (class "Default")
      (node (ref "N") (pin "4") (pinfunction "4_4") (pintype "passive"))
    )
  )
)
